# electrode_1.net
KiCad netlist of a schematic drawn in Altium Designer
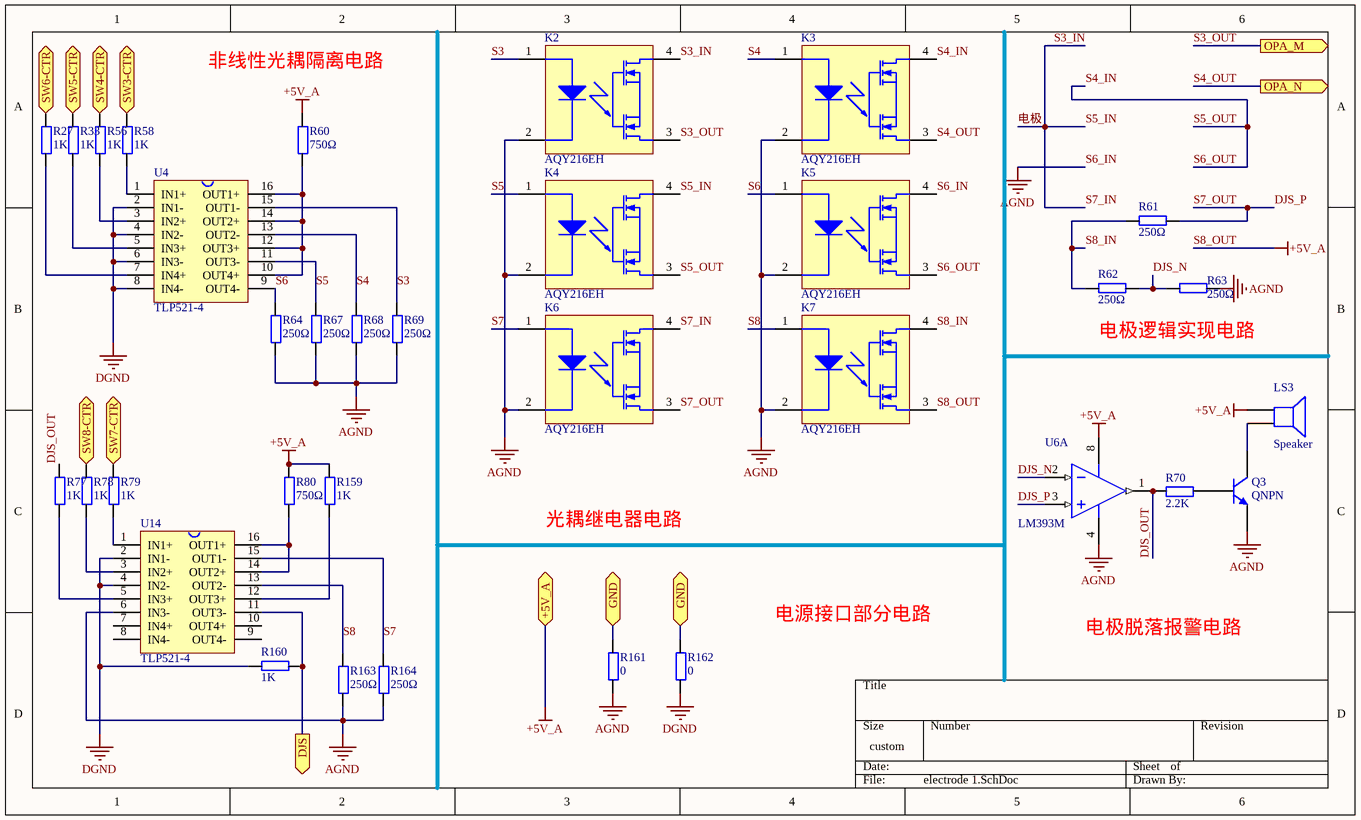
[diagram p0: electrode 1.SchDoc]

(export (version "E")
  (design (tool "Eeschema 10.0.6"))
  (components
    (comp (ref "K2")
      (value "AQY216EH")
      (footprint "PNSC-DIP4_V")
      (fields (field (name "MANUFACTURER") "Panasonic"))
      (libsource (lib "dianfazhan") (part "AQY216EH"))
    )
    (comp (ref "K3")
      (value "AQY216EH")
      (footprint "PNSC-DIP4_V")
      (fields (field (name "MANUFACTURER") "Panasonic"))
      (libsource (lib "dianfazhan") (part "AQY216EH"))
    )
    (comp (ref "K4")
      (value "AQY216EH")
      (footprint "PNSC-DIP4_V")
      (fields (field (name "MANUFACTURER") "Panasonic"))
      (libsource (lib "dianfazhan") (part "AQY216EH"))
    )
    (comp (ref "K5")
      (value "AQY216EH")
      (footprint "PNSC-DIP4_V")
      (fields (field (name "MANUFACTURER") "Panasonic"))
      (libsource (lib "dianfazhan") (part "AQY216EH"))
    )
    (comp (ref "K6")
      (value "AQY216EH")
      (footprint "PNSC-DIP4_V")
      (fields (field (name "MANUFACTURER") "Panasonic"))
      (libsource (lib "dianfazhan") (part "AQY216EH"))
    )
    (comp (ref "K7")
      (value "AQY216EH")
      (footprint "PNSC-DIP4_V")
      (fields (field (name "MANUFACTURER") "Panasonic"))
      (libsource (lib "dianfazhan") (part "AQY216EH"))
    )
    (comp (ref "LS3")
      (value "Speaker")
      (footprint "PIN2")
      (description "Loudspeaker")
      (fields (field (name "PUBLISHER") "Altium Limited"))
      (libsource (lib "Miscellaneous Devices") (part "Speaker"))
    )
    (comp (ref "Q3")
      (value "QNPN")
      (footprint "SOT-23B_N")
      (description "NPN Bipolar Transistor")
      (fields (field (name "PUBLISHER") "Altium Limited"))
      (libsource (lib "Miscellaneous Devices") (part "QNPN"))
    )
    (comp (ref "R27") (value "1K") (footprint "0603P") (libsource (lib "MiniSTM32 V3.0封装库") (part "R")))
    (comp (ref "R33") (value "1K") (footprint "0603P") (libsource (lib "MiniSTM32 V3.0封装库") (part "R")))
    (comp (ref "R56") (value "1K") (footprint "0603P") (libsource (lib "MiniSTM32 V3.0封装库") (part "R")))
    (comp (ref "R58") (value "1K") (footprint "0603P") (libsource (lib "MiniSTM32 V3.0封装库") (part "R")))
    (comp (ref "R60") (value "750Ω") (footprint "0603P") (libsource (lib "MiniSTM32 V3.0封装库") (part "R")))
    (comp (ref "R61") (value "250Ω") (footprint "0603P") (libsource (lib "MiniSTM32 V3.0封装库") (part "R")))
    (comp (ref "R62") (value "250Ω") (footprint "0603P") (libsource (lib "MiniSTM32 V3.0封装库") (part "R")))
    (comp (ref "R63") (value "250Ω") (footprint "0603P") (libsource (lib "MiniSTM32 V3.0封装库") (part "R")))
    (comp (ref "R64") (value "250Ω") (footprint "0603P") (libsource (lib "MiniSTM32 V3.0封装库") (part "R")))
    (comp (ref "R67") (value "250Ω") (footprint "0603P") (libsource (lib "MiniSTM32 V3.0封装库") (part "R")))
    (comp (ref "R68") (value "250Ω") (footprint "0603P") (libsource (lib "MiniSTM32 V3.0封装库") (part "R")))
    (comp (ref "R69") (value "250Ω") (footprint "0603P") (libsource (lib "MiniSTM32 V3.0封装库") (part "R")))
    (comp (ref "R70") (value "2.2K") (footprint "0603P") (libsource (lib "MiniSTM32 V3.0封装库") (part "R")))
    (comp (ref "R77") (value "1K") (footprint "0603P") (libsource (lib "MiniSTM32 V3.0封装库") (part "R")))
    (comp (ref "R78") (value "1K") (footprint "0603P") (libsource (lib "MiniSTM32 V3.0封装库") (part "R")))
    (comp (ref "R79") (value "1K") (footprint "0603P") (libsource (lib "MiniSTM32 V3.0封装库") (part "R")))
    (comp (ref "R80") (value "750Ω") (footprint "0603P") (libsource (lib "MiniSTM32 V3.0封装库") (part "R")))
    (comp (ref "R159") (value "1K") (footprint "0603P") (libsource (lib "MiniSTM32 V3.0封装库") (part "R")))
    (comp (ref "R160") (value "1K") (footprint "0603P") (libsource (lib "MiniSTM32 V3.0封装库") (part "R")))
    (comp (ref "R161") (value "0") (footprint "0603P") (libsource (lib "MiniSTM32 V3.0封装库") (part "R")))
    (comp (ref "R162") (value "0") (footprint "0603P") (libsource (lib "MiniSTM32 V3.0封装库") (part "R")))
    (comp (ref "R163") (value "250Ω") (footprint "0603P") (libsource (lib "MiniSTM32 V3.0封装库") (part "R")))
    (comp (ref "R164") (value "250Ω") (footprint "0603P") (libsource (lib "MiniSTM32 V3.0封装库") (part "R")))
    (comp (ref "U4") (value "TLP521-4") (footprint "11-20A3") (libsource (lib "dinafa") (part "TLP521")))
    (comp (ref "U6")
      (value "LM393M")
      (footprint "M08A_L")
      (description "Low Power Low Offset Voltage Dual Comparator, 8-pin Narrow SOIC")
      (fields (field (name "MANUFACTURER") "National Semiconductor"))
      (libsource (lib "dianfazhan") (part "LM393M"))
    )
    (comp (ref "U14") (value "TLP521-4") (footprint "11-20A3") (libsource (lib "dinafa") (part "TLP521")))
  )
  (nets
    (net (code "1") (name "+5V_A") (class "Default")
      (node (ref "K7") (pin "3") (pinfunction "3_3") (pintype "passive"))
      (node (ref "LS3") (pin "1") (pinfunction "1_1") (pintype "passive"))
      (node (ref "R159") (pin "2") (pintype "passive"))
      (node (ref "R60") (pin "2") (pintype "passive"))
      (node (ref "R80") (pin "2") (pintype "passive"))
      (node (ref "U6") (pin "8") (pinfunction "V+_8") (pintype "power_in"))
    )
    (net (code "2") (name "/DJS") (class "Default")
      (node (ref "R160") (pin "1") (pintype "passive"))
      (node (ref "U14") (pin "11") (pinfunction "OUT3-_11") (pintype "passive"))
    )
    (net (code "3") (name "/DJS_N") (class "Default")
      (node (ref "R62") (pin "1") (pintype "passive"))
      (node (ref "R63") (pin "2") (pintype "passive"))
      (node (ref "U6") (pin "2") (pinfunction "INA-_2") (pintype "input"))
    )
    (net (code "4") (name "/DJS_OUT") (class "Default")
      (node (ref "R70") (pin "1") (pintype "passive"))
      (node (ref "R77") (pin "2") (pintype "passive"))
      (node (ref "U6") (pin "1") (pinfunction "OUTA_1") (pintype "output"))
    )
    (net (code "5") (name "/DJS_P") (class "Default")
      (node (ref "K6") (pin "3") (pinfunction "3_3") (pintype "passive"))
      (node (ref "R61") (pin "1") (pintype "passive"))
      (node (ref "U6") (pin "3") (pinfunction "INA+_3") (pintype "input"))
    )
    (net (code "6") (name "/GND") (class "Default")
      (node (ref "R161") (pin "2") (pintype "passive"))
      (node (ref "R162") (pin "2") (pintype "passive"))
    )
    (net (code "7") (name "/S3") (class "Default")
      (node (ref "K2") (pin "1") (pinfunction "1_1") (pintype "passive"))
      (node (ref "R69") (pin "2") (pintype "passive"))
      (node (ref "U4") (pin "15") (pinfunction "OUT1-_15") (pintype "passive"))
    )
    (net (code "8") (name "/S3_IN") (class "Default")
      (node (ref "K2") (pin "4") (pinfunction "4_4") (pintype "passive"))
      (node (ref "K4") (pin "4") (pinfunction "4_4") (pintype "passive"))
      (node (ref "K6") (pin "4") (pinfunction "4_4") (pintype "passive"))
    )
    (net (code "9") (name "/S3_OUT") (class "Default")
      (node (ref "K2") (pin "3") (pinfunction "3_3") (pintype "passive"))
    )
    (net (code "10") (name "/S4") (class "Default")
      (node (ref "K3") (pin "1") (pinfunction "1_1") (pintype "passive"))
      (node (ref "R68") (pin "2") (pintype "passive"))
      (node (ref "U4") (pin "13") (pinfunction "OUT2-_13") (pintype "passive"))
    )
    (net (code "11") (name "/S4_IN") (class "Default")
      (node (ref "K3") (pin "4") (pinfunction "4_4") (pintype "passive"))
      (node (ref "K4") (pin "3") (pinfunction "3_3") (pintype "passive"))
      (node (ref "K5") (pin "3") (pinfunction "3_3") (pintype "passive"))
    )
    (net (code "12") (name "/S4_OUT") (class "Default")
      (node (ref "K3") (pin "3") (pinfunction "3_3") (pintype "passive"))
    )
    (net (code "13") (name "/S5") (class "Default")
      (node (ref "K4") (pin "1") (pinfunction "1_1") (pintype "passive"))
      (node (ref "R67") (pin "2") (pintype "passive"))
      (node (ref "U4") (pin "11") (pinfunction "OUT3-_11") (pintype "passive"))
    )
    (net (code "14") (name "/S6") (class "Default")
      (node (ref "K5") (pin "1") (pinfunction "1_1") (pintype "passive"))
      (node (ref "R64") (pin "2") (pintype "passive"))
      (node (ref "U4") (pin "9") (pinfunction "OUT4-_9") (pintype "passive"))
    )
    (net (code "15") (name "/S7") (class "Default")
      (node (ref "K6") (pin "1") (pinfunction "1_1") (pintype "passive"))
      (node (ref "R164") (pin "2") (pintype "passive"))
      (node (ref "U14") (pin "15") (pinfunction "OUT1-_15") (pintype "passive"))
    )
    (net (code "16") (name "/S8") (class "Default")
      (node (ref "K7") (pin "1") (pinfunction "1_1") (pintype "passive"))
      (node (ref "R163") (pin "2") (pintype "passive"))
      (node (ref "U14") (pin "13") (pinfunction "OUT2-_13") (pintype "passive"))
    )
    (net (code "17") (name "/S8_IN") (class "Default")
      (node (ref "K7") (pin "4") (pinfunction "4_4") (pintype "passive"))
      (node (ref "R61") (pin "2") (pintype "passive"))
      (node (ref "R62") (pin "2") (pintype "passive"))
    )
    (net (code "18") (name "/SW3-CTR") (class "Default") (node (ref "R58") (pin "2") (pintype "passive")))
    (net (code "19") (name "/SW4-CTR") (class "Default") (node (ref "R56") (pin "2") (pintype "passive")))
    (net (code "20") (name "/SW5-CTR") (class "Default") (node (ref "R33") (pin "2") (pintype "passive")))
    (net (code "21") (name "/SW6-CTR") (class "Default") (node (ref "R27") (pin "2") (pintype "passive")))
    (net (code "22") (name "/SW7-CTR") (class "Default") (node (ref "R79") (pin "2") (pintype "passive")))
    (net (code "23") (name "/SW8-CTR") (class "Default") (node (ref "R78") (pin "2") (pintype "passive")))
    (net (code "24") (name "AGND") (class "Default")
      (node (ref "K2") (pin "2") (pinfunction "2_2") (pintype "passive"))
      (node (ref "K3") (pin "2") (pinfunction "2_2") (pintype "passive"))
      (node (ref "K4") (pin "2") (pinfunction "2_2") (pintype "passive"))
      (node (ref "K5") (pin "2") (pinfunction "2_2") (pintype "passive"))
      (node (ref "K5") (pin "4") (pinfunction "4_4") (pintype "passive"))
      (node (ref "K6") (pin "2") (pinfunction "2_2") (pintype "passive"))
      (node (ref "K7") (pin "2") (pinfunction "2_2") (pintype "passive"))
      (node (ref "Q3") (pin "3") (pinfunction "E_3") (pintype "passive"))
      (node (ref "R161") (pin "1") (pintype "passive"))
      (node (ref "R163") (pin "1") (pintype "passive"))
      (node (ref "R164") (pin "1") (pintype "passive"))
      (node (ref "R63") (pin "1") (pintype "passive"))
      (node (ref "R64") (pin "1") (pintype "passive"))
      (node (ref "R67") (pin "1") (pintype "passive"))
      (node (ref "R68") (pin "1") (pintype "passive"))
      (node (ref "R69") (pin "1") (pintype "passive"))
      (node (ref "U14") (pin "6") (pinfunction "IN3-_6") (pintype "passive"))
      (node (ref "U6") (pin "4") (pinfunction "GND_4") (pintype "power_in"))
    )
    (net (code "25") (name "DGND") (class "Default")
      (node (ref "R160") (pin "2") (pintype "passive"))
      (node (ref "R162") (pin "1") (pintype "passive"))
      (node (ref "U14") (pin "2") (pinfunction "IN1-_2") (pintype "passive"))
      (node (ref "U14") (pin "4") (pinfunction "IN2-_4") (pintype "passive"))
      (node (ref "U4") (pin "2") (pinfunction "IN1-_2") (pintype "passive"))
      (node (ref "U4") (pin "4") (pinfunction "IN2-_4") (pintype "passive"))
      (node (ref "U4") (pin "6") (pinfunction "IN3-_6") (pintype "passive"))
      (node (ref "U4") (pin "8") (pinfunction "IN4-_8") (pintype "passive"))
    )
    (net (code "26") (name "Net-(Q3-B)") (class "Default")
      (node (ref "Q3") (pin "2") (pinfunction "B_2") (pintype "passive"))
      (node (ref "R70") (pin "2") (pintype "passive"))
    )
    (net (code "27") (name "Net-(Q3-C)") (class "Default")
      (node (ref "LS3") (pin "2") (pinfunction "2_2") (pintype "passive"))
      (node (ref "Q3") (pin "1") (pinfunction "C_1") (pintype "passive"))
    )
    (net (code "28") (name "Net-(U4-IN1+)") (class "Default")
      (node (ref "R58") (pin "1") (pintype "passive"))
      (node (ref "U4") (pin "1") (pinfunction "IN1+_1") (pintype "passive"))
    )
    (net (code "29") (name "Net-(U4-IN2+)") (class "Default")
      (node (ref "R56") (pin "1") (pintype "passive"))
      (node (ref "U4") (pin "3") (pinfunction "IN2+_3") (pintype "passive"))
    )
    (net (code "30") (name "Net-(U4-IN3+)") (class "Default")
      (node (ref "R33") (pin "1") (pintype "passive"))
      (node (ref "U4") (pin "5") (pinfunction "IN3+_5") (pintype "passive"))
    )
    (net (code "31") (name "Net-(U4-IN4+)") (class "Default")
      (node (ref "R27") (pin "1") (pintype "passive"))
      (node (ref "U4") (pin "7") (pinfunction "IN4+_7") (pintype "passive"))
    )
    (net (code "32") (name "Net-(U4-OUT1+)") (class "Default")
      (node (ref "R60") (pin "1") (pintype "passive"))
      (node (ref "U4") (pin "10") (pinfunction "OUT4+_10") (pintype "passive"))
      (node (ref "U4") (pin "12") (pinfunction "OUT3+_12") (pintype "passive"))
      (node (ref "U4") (pin "14") (pinfunction "OUT2+_14") (pintype "passive"))
      (node (ref "U4") (pin "16") (pinfunction "OUT1+_16") (pintype "passive"))
    )
    (net (code "33") (name "Net-(U14-IN1+)") (class "Default")
      (node (ref "R79") (pin "1") (pintype "passive"))
      (node (ref "U14") (pin "1") (pinfunction "IN1+_1") (pintype "passive"))
    )
    (net (code "34") (name "Net-(U14-IN2+)") (class "Default")
      (node (ref "R78") (pin "1") (pintype "passive"))
      (node (ref "U14") (pin "3") (pinfunction "IN2+_3") (pintype "passive"))
    )
    (net (code "35") (name "Net-(U14-IN3+)") (class "Default")
      (node (ref "R77") (pin "1") (pintype "passive"))
      (node (ref "U14") (pin "5") (pinfunction "IN3+_5") (pintype "passive"))
    )
    (net (code "36") (name "Net-(U14-OUT1+)") (class "Default")
      (node (ref "R80") (pin "1") (pintype "passive"))
      (node (ref "U14") (pin "14") (pinfunction "OUT2+_14") (pintype "passive"))
      (node (ref "U14") (pin "16") (pinfunction "OUT1+_16") (pintype "passive"))
    )
    (net (code "37") (name "Net-(U14-OUT3+)") (class "Default")
      (node (ref "R159") (pin "1") (pintype "passive"))
      (node (ref "U14") (pin "12") (pinfunction "OUT3+_12") (pintype "passive"))
    )
    (net (code "38") (name "unconnected-(U14-IN4+-Pad7)") (class "Default")
      (node (ref "U14") (pin "7") (pinfunction "IN4+_7") (pintype "passive"))
    )
    (net (code "39") (name "unconnected-(U14-IN4--Pad8)") (class "Default")
      (node (ref "U14") (pin "8") (pinfunction "IN4-_8") (pintype "passive"))
    )
    (net (code "40") (name "unconnected-(U14-OUT4+-Pad10)") (class "Default")
      (node (ref "U14") (pin "10") (pinfunction "OUT4+_10") (pintype "passive"))
    )
    (net (code "41") (name "unconnected-(U14-OUT4--Pad9)") (class "Default")
      (node (ref "U14") (pin "9") (pinfunction "OUT4-_9") (pintype "passive"))
    )
  )
)
